# lte.net
KiCad netlist of a schematic drawn in Altium Designer
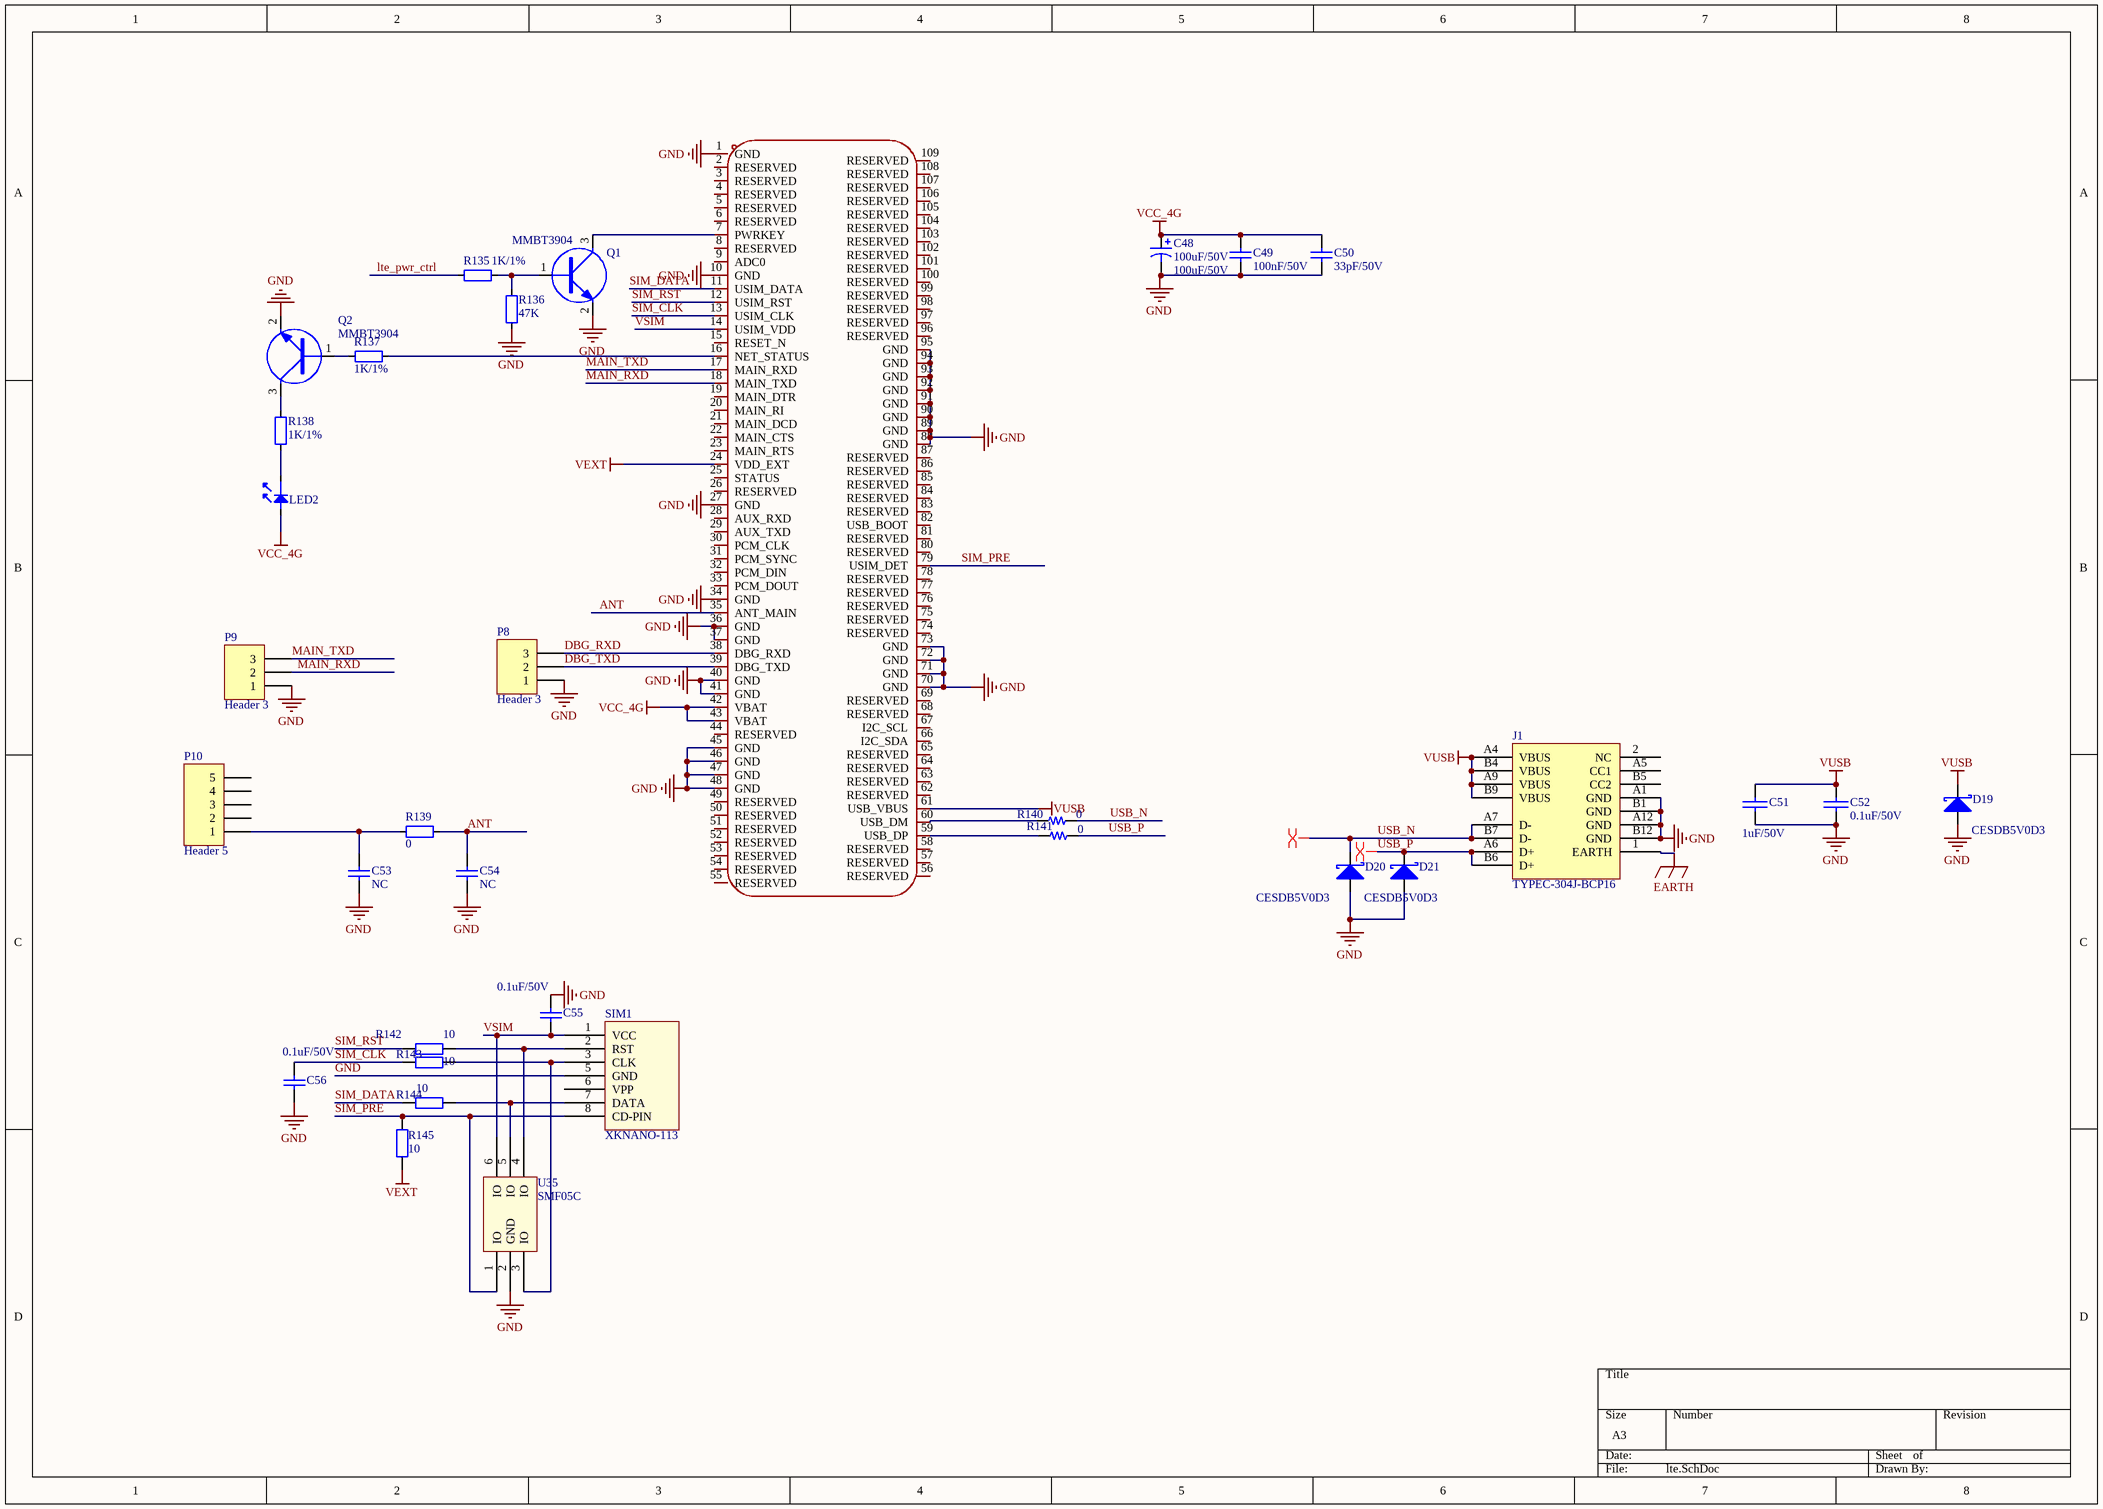
[diagram p0: lte.SchDoc]

(export (version "E")
  (design (tool "Eeschema 10.0.6"))
  (components
    (comp (ref "C48")
      (value "100uF/50V")
      (footprint "CAP-SMD_BD6.3-L6.5-W6.5-LS7.0-FD:CAP-SMD_BD6.3-L6.5-W6.5-LS7.0-FD")
      (description "Polarized Capacitor (Surface Mount)")
      (fields (field (name "ALTIUM_VALUE") "100uF/50V"))
      (libsource (lib "Miscellaneous Devices") (part "Cap Pol3"))
    )
    (comp (ref "C49")
      (value "100nF/50V")
      (footprint "0603C")
      (description "Capacitor")
      (libsource (lib "Miscellaneous Devices") (part "Cap"))
    )
    (comp (ref "C50")
      (value "33pF/50V")
      (footprint "0603C")
      (description "Capacitor")
      (libsource (lib "Miscellaneous Devices") (part "Cap"))
    )
    (comp (ref "C51")
      (value "1uF/50V")
      (footprint "CAPC1608X092N_0603")
      (fields (field (name "PARTNUMBER") "CL10A105KB8NNNC"))
      (libsource (lib "SM") (part "CAP"))
    )
    (comp (ref "C52")
      (value "0.1uF/50V")
      (footprint "CAPC1608X092N_0603")
      (fields (field (name "PARTNUMBER") "CC0603KRX7R9BB104"))
      (libsource (lib "SM") (part "CAP"))
    )
    (comp (ref "C53")
      (value "NC")
      (footprint "0603c")
      (description "Capacitor")
      (libsource (lib "Miscellaneous Devices") (part "Cap"))
    )
    (comp (ref "C54")
      (value "NC")
      (footprint "0603c")
      (description "Capacitor")
      (libsource (lib "Miscellaneous Devices") (part "Cap"))
    )
    (comp (ref "C55")
      (value "0.1uF/50V")
      (footprint "0603c")
      (description "Capacitor")
      (libsource (lib "Miscellaneous Devices") (part "Cap"))
    )
    (comp (ref "C56")
      (value "0.1uF/50V")
      (footprint "0603c")
      (description "Capacitor")
      (libsource (lib "Miscellaneous Devices") (part "Cap"))
    )
    (comp (ref "D19") (value "CESDB5V0D3") (footprint "SOD323") (libsource (lib "*") (part "DIODE S")))
    (comp (ref "D20") (value "CESDB5V0D3") (footprint "SOD323") (libsource (lib "*") (part "DIODE S")))
    (comp (ref "D21") (value "CESDB5V0D3") (footprint "SOD323") (libsource (lib "*") (part "DIODE S")))
    (comp (ref "J1")
      (value "TYPEC-304J-BCP16")
      (footprint "TYPEC_16P")
      (libsource (lib "Schlib_20110825") (part "TYPE C_16P"))
    )
    (comp (ref "LED2")
      (value "LED_Green_19-217")
      (footprint "0603led")
      (libsource (lib "RC_M_D_00") (part "LED_Green_19-217"))
    )
    (comp (ref "P8")
      (value "Header 3")
      (footprint "HDR1X3")
      (description "Header, 3-Pin")
      (libsource (lib "Miscellaneous Connectors") (part "Header 3"))
    )
    (comp (ref "P9")
      (value "Header 3")
      (footprint "HDR1X3")
      (description "Header, 3-Pin")
      (libsource (lib "Miscellaneous Connectors") (part "Header 3"))
    )
    (comp (ref "P10")
      (value "Header 5")
      (footprint "controller_V1.3.1:KH-SMA-KE-Z")
      (description "Header, 5-Pin")
      (libsource (lib "Miscellaneous Connectors") (part "Header 5"))
    )
    (comp (ref "Q1")
      (value "MMBT3904")
      (footprint "SOT23-3")
      (libsource (lib "CenLib") (part "NPN_MMBT3904"))
    )
    (comp (ref "Q2")
      (value "MMBT3904")
      (footprint "SOT23-3")
      (libsource (lib "CenLib") (part "NPN_MMBT3904"))
    )
    (comp (ref "R135") (value "1K/1%") (footprint "0603R") (libsource (lib "RC_M_D_00") (part "RES0603")))
    (comp (ref "R136") (value "47K") (footprint "0603r") (libsource (lib "RC_M_D_00") (part "RES0603")))
    (comp (ref "R137") (value "1K/1%") (footprint "0603r") (libsource (lib "RC_M_D_00") (part "RES0603")))
    (comp (ref "R138") (value "1K/1%") (footprint "0603R") (libsource (lib "RC_M_D_00") (part "RES0603")))
    (comp (ref "R139") (value "0") (footprint "0603r") (libsource (lib "RC_M_D_00") (part "RES0603")))
    (comp (ref "R140")
      (value "0")
      (footprint "RESC1608X055N_0603")
      (fields (field (name "PARTNUMBER") "RC0603FR-071KL"))
      (libsource (lib "JRJ_1") (part "R"))
    )
    (comp (ref "R141")
      (value "0")
      (footprint "RESC1608X055N_0603")
      (fields (field (name "PARTNUMBER") "RC0603FR-071KL"))
      (libsource (lib "JRJ_1") (part "R"))
    )
    (comp (ref "R142")
      (value "10")
      (footprint "0603r")
      (description "Resistor")
      (libsource (lib "Miscellaneous Devices") (part "Res2"))
    )
    (comp (ref "R143")
      (value "10")
      (footprint "0603r")
      (description "Resistor")
      (libsource (lib "Miscellaneous Devices") (part "Res2"))
    )
    (comp (ref "R144")
      (value "10")
      (footprint "0603r")
      (description "Resistor")
      (libsource (lib "Miscellaneous Devices") (part "Res2"))
    )
    (comp (ref "R145")
      (value "10")
      (footprint "0603r")
      (description "Resistor")
      (libsource (lib "") (part "Res2_1"))
    )
    (comp (ref "SIM1") (value "XKNANO-113") (footprint "Nano SIM") (libsource (lib "lm") (part "nano sim")))
    (comp (ref "U34")
      (value "EC800ECNNQ-N03-SNNSA")
      (footprint "LCC-LGA-109_L17.7-W15.8-P1.10_MC661:LCC-LGA-109_L17.7-W15.8-P1.10_MC661")
      (libsource (lib "altium-import") (part "root_0_EC800ECNNQ-N03-SNNSA_"))
    )
    (comp (ref "U35") (value "SMF05C") (footprint "sc70-6l") (libsource (lib "lm") (part "SMF05C")))
  )
  (nets
    (net (code "1") (name "/ANT") (class "Default")
      (node (ref "C54") (pin "1") (pinfunction "1_1") (pintype "passive"))
      (node (ref "R139") (pin "1") (pinfunction "1_1") (pintype "passive"))
      (node (ref "U34") (pin "35") (pinfunction "ANT_MAIN_35") (pintype "passive"))
    )
    (net (code "2") (name "/DBG_RXD") (class "Default")
      (node (ref "P8") (pin "3") (pinfunction "3_3") (pintype "passive"))
      (node (ref "U34") (pin "38") (pinfunction "DBG_RXD_38") (pintype "passive"))
    )
    (net (code "3") (name "/DBG_TXD") (class "Default")
      (node (ref "P8") (pin "2") (pinfunction "2_2") (pintype "passive"))
      (node (ref "U34") (pin "39") (pinfunction "DBG_TXD_39") (pintype "passive"))
    )
    (net (code "4") (name "/MAIN_RXD") (class "Default")
      (node (ref "P9") (pin "2") (pinfunction "2_2") (pintype "passive"))
      (node (ref "U34") (pin "18") (pinfunction "MAIN_TXD_18") (pintype "passive"))
    )
    (net (code "5") (name "/MAIN_TXD") (class "Default")
      (node (ref "P9") (pin "3") (pinfunction "3_3") (pintype "passive"))
      (node (ref "U34") (pin "17") (pinfunction "MAIN_RXD_17") (pintype "passive"))
    )
    (net (code "6") (name "/SIM_CLK") (class "Default")
      (node (ref "C56") (pin "1") (pinfunction "1_1") (pintype "passive"))
      (node (ref "R143") (pin "2") (pinfunction "2_2") (pintype "passive"))
      (node (ref "U34") (pin "13") (pinfunction "USIM_CLK_13") (pintype "passive"))
    )
    (net (code "7") (name "/SIM_DATA") (class "Default")
      (node (ref "R144") (pin "2") (pinfunction "2_2") (pintype "passive"))
      (node (ref "U34") (pin "11") (pinfunction "USIM_DATA_11") (pintype "passive"))
    )
    (net (code "8") (name "/SIM_PRE") (class "Default")
      (node (ref "R145") (pin "1") (pinfunction "1_1") (pintype "passive"))
      (node (ref "SIM1") (pin "8") (pinfunction "CD-PIN_8") (pintype "passive"))
      (node (ref "U34") (pin "79") (pinfunction "USIM_DET_79") (pintype "passive"))
      (node (ref "U35") (pin "1") (pinfunction "IO_1") (pintype "passive"))
    )
    (net (code "9") (name "/SIM_RST") (class "Default")
      (node (ref "R142") (pin "2") (pinfunction "2_2") (pintype "passive"))
      (node (ref "U34") (pin "12") (pinfunction "USIM_RST_12") (pintype "passive"))
    )
    (net (code "10") (name "/USB_N") (class "Default")
      (node (ref "D20") (pin "2") (pinfunction "K_2") (pintype "passive"))
      (node (ref "J1") (pin "A7") (pinfunction "D-_A7") (pintype "passive"))
      (node (ref "J1") (pin "B7") (pinfunction "D-_B7") (pintype "passive"))
      (node (ref "R140") (pin "1") (pintype "passive"))
    )
    (net (code "11") (name "/USB_P") (class "Default")
      (node (ref "D21") (pin "2") (pinfunction "K_2") (pintype "passive"))
      (node (ref "J1") (pin "A6") (pinfunction "D+_A6") (pintype "passive"))
      (node (ref "J1") (pin "B6") (pinfunction "D+_B6") (pintype "passive"))
      (node (ref "R141") (pin "1") (pintype "passive"))
    )
    (net (code "12") (name "/VSIM") (class "Default")
      (node (ref "C55") (pin "2") (pinfunction "2_2") (pintype "passive"))
      (node (ref "SIM1") (pin "1") (pinfunction "VCC_1") (pintype "passive"))
      (node (ref "U34") (pin "14") (pinfunction "USIM_VDD_14") (pintype "passive"))
      (node (ref "U35") (pin "6") (pinfunction "IO_6") (pintype "passive"))
    )
    (net (code "13") (name "/lte_pwr_ctrl") (class "Default")
      (node (ref "R135") (pin "1") (pinfunction "1_1") (pintype "passive"))
    )
    (net (code "14") (name "EARTH") (class "Default")
      (node (ref "J1") (pin "1") (pinfunction "EARTH_1") (pintype "passive"))
    )
    (net (code "15") (name "GND") (class "Default")
      (node (ref "C48") (pin "2") (pinfunction "2_2") (pintype "passive"))
      (node (ref "C49") (pin "1") (pinfunction "1_1") (pintype "passive"))
      (node (ref "C50") (pin "1") (pinfunction "1_1") (pintype "passive"))
      (node (ref "C51") (pin "1") (pinfunction "1_1") (pintype "passive"))
      (node (ref "C52") (pin "1") (pinfunction "1_1") (pintype "passive"))
      (node (ref "C53") (pin "2") (pinfunction "2_2") (pintype "passive"))
      (node (ref "C54") (pin "2") (pinfunction "2_2") (pintype "passive"))
      (node (ref "C55") (pin "1") (pinfunction "1_1") (pintype "passive"))
      (node (ref "C56") (pin "2") (pinfunction "2_2") (pintype "passive"))
      (node (ref "D19") (pin "1") (pinfunction "A_1") (pintype "passive"))
      (node (ref "D20") (pin "1") (pinfunction "A_1") (pintype "passive"))
      (node (ref "D21") (pin "1") (pinfunction "A_1") (pintype "passive"))
      (node (ref "J1") (pin "A1") (pinfunction "GND_A1") (pintype "passive"))
      (node (ref "J1") (pin "A12") (pinfunction "GND_A12") (pintype "passive"))
      (node (ref "J1") (pin "B1") (pinfunction "GND_B1") (pintype "passive"))
      (node (ref "J1") (pin "B12") (pinfunction "GND_B12") (pintype "passive"))
      (node (ref "P8") (pin "1") (pinfunction "1_1") (pintype "passive"))
      (node (ref "P9") (pin "1") (pinfunction "1_1") (pintype "passive"))
      (node (ref "Q1") (pin "2") (pinfunction "E_2") (pintype "passive"))
      (node (ref "Q2") (pin "2") (pinfunction "E_2") (pintype "passive"))
      (node (ref "R136") (pin "1") (pinfunction "1_1") (pintype "passive"))
      (node (ref "SIM1") (pin "5") (pinfunction "GND_5") (pintype "passive"))
      (node (ref "U34") (pin "1") (pinfunction "GND_1") (pintype "passive"))
      (node (ref "U34") (pin "10") (pinfunction "GND_10") (pintype "passive"))
      (node (ref "U34") (pin "27") (pinfunction "GND_27") (pintype "passive"))
      (node (ref "U34") (pin "34") (pinfunction "GND_34") (pintype "passive"))
      (node (ref "U34") (pin "36") (pinfunction "GND_36") (pintype "passive"))
      (node (ref "U34") (pin "37") (pinfunction "GND_37") (pintype "passive"))
      (node (ref "U34") (pin "40") (pinfunction "GND_40") (pintype "passive"))
      (node (ref "U34") (pin "41") (pinfunction "GND_41") (pintype "passive"))
      (node (ref "U34") (pin "45") (pinfunction "GND_45") (pintype "passive"))
      (node (ref "U34") (pin "46") (pinfunction "GND_46") (pintype "passive"))
      (node (ref "U34") (pin "47") (pinfunction "GND_47") (pintype "passive"))
      (node (ref "U34") (pin "48") (pinfunction "GND_48") (pintype "passive"))
      (node (ref "U34") (pin "70") (pinfunction "GND_70") (pintype "passive"))
      (node (ref "U34") (pin "71") (pinfunction "GND_71") (pintype "passive"))
      (node (ref "U34") (pin "72") (pinfunction "GND_72") (pintype "passive"))
      (node (ref "U34") (pin "73") (pinfunction "GND_73") (pintype "passive"))
      (node (ref "U34") (pin "88") (pinfunction "GND_88") (pintype "passive"))
      (node (ref "U34") (pin "89") (pinfunction "GND_89") (pintype "passive"))
      (node (ref "U34") (pin "90") (pinfunction "GND_90") (pintype "passive"))
      (node (ref "U34") (pin "91") (pinfunction "GND_91") (pintype "passive"))
      (node (ref "U34") (pin "92") (pinfunction "GND_92") (pintype "passive"))
      (node (ref "U34") (pin "93") (pinfunction "GND_93") (pintype "passive"))
      (node (ref "U34") (pin "94") (pinfunction "GND_94") (pintype "passive"))
      (node (ref "U34") (pin "95") (pinfunction "GND_95") (pintype "passive"))
      (node (ref "U35") (pin "2") (pinfunction "GND_2") (pintype "passive"))
    )
    (net (code "16") (name "Net-(C53-Pad1)") (class "Default")
      (node (ref "C53") (pin "1") (pinfunction "1_1") (pintype "passive"))
      (node (ref "P10") (pin "1") (pinfunction "1_1") (pintype "passive"))
      (node (ref "R139") (pin "2") (pinfunction "2_2") (pintype "passive"))
    )
    (net (code "17") (name "Net-(LED2-Pad2)") (class "Default")
      (node (ref "LED2") (pin "2") (pinfunction "2_2") (pintype "passive"))
      (node (ref "R138") (pin "1") (pinfunction "1_1") (pintype "passive"))
    )
    (net (code "18") (name "Net-(Q1-B)") (class "Default")
      (node (ref "Q1") (pin "1") (pinfunction "B_1") (pintype "passive"))
      (node (ref "R135") (pin "2") (pinfunction "2_2") (pintype "passive"))
      (node (ref "R136") (pin "2") (pinfunction "2_2") (pintype "passive"))
    )
    (net (code "19") (name "Net-(Q1-C)") (class "Default")
      (node (ref "Q1") (pin "3") (pinfunction "C_3") (pintype "passive"))
      (node (ref "U34") (pin "7") (pinfunction "PWRKEY_7") (pintype "passive"))
    )
    (net (code "20") (name "Net-(Q2-B)") (class "Default")
      (node (ref "Q2") (pin "1") (pinfunction "B_1") (pintype "passive"))
      (node (ref "R137") (pin "2") (pinfunction "2_2") (pintype "passive"))
    )
    (net (code "21") (name "Net-(Q2-C)") (class "Default")
      (node (ref "Q2") (pin "3") (pinfunction "C_3") (pintype "passive"))
      (node (ref "R138") (pin "2") (pinfunction "2_2") (pintype "passive"))
    )
    (net (code "22") (name "Net-(SIM1-CLK)") (class "Default")
      (node (ref "R143") (pin "1") (pinfunction "1_1") (pintype "passive"))
      (node (ref "SIM1") (pin "3") (pinfunction "CLK_3") (pintype "passive"))
      (node (ref "U35") (pin "3") (pinfunction "IO_3") (pintype "passive"))
    )
    (net (code "23") (name "Net-(SIM1-DATA)") (class "Default")
      (node (ref "R144") (pin "1") (pinfunction "1_1") (pintype "passive"))
      (node (ref "SIM1") (pin "7") (pinfunction "DATA_7") (pintype "passive"))
      (node (ref "U35") (pin "5") (pinfunction "IO_5") (pintype "passive"))
    )
    (net (code "24") (name "Net-(SIM1-RST)") (class "Default")
      (node (ref "R142") (pin "1") (pinfunction "1_1") (pintype "passive"))
      (node (ref "SIM1") (pin "2") (pinfunction "RST_2") (pintype "passive"))
      (node (ref "U35") (pin "4") (pinfunction "IO_4") (pintype "passive"))
    )
    (net (code "25") (name "Net-(U34-NET_STATUS)") (class "Default")
      (node (ref "R137") (pin "1") (pinfunction "1_1") (pintype "passive"))
      (node (ref "U34") (pin "16") (pinfunction "NET_STATUS_16") (pintype "passive"))
    )
    (net (code "26") (name "Net-(U34-USB_DM)") (class "Default")
      (node (ref "R140") (pin "2") (pintype "passive"))
      (node (ref "U34") (pin "60") (pinfunction "USB_DM_60") (pintype "passive"))
    )
    (net (code "27") (name "Net-(U34-USB_DP)") (class "Default")
      (node (ref "R141") (pin "2") (pintype "passive"))
      (node (ref "U34") (pin "59") (pinfunction "USB_DP_59") (pintype "passive"))
    )
    (net (code "28") (name "VCC_4G") (class "Default")
      (node (ref "C48") (pin "1") (pinfunction "1_1") (pintype "passive"))
      (node (ref "C49") (pin "2") (pinfunction "2_2") (pintype "passive"))
      (node (ref "C50") (pin "2") (pinfunction "2_2") (pintype "passive"))
      (node (ref "LED2") (pin "1") (pinfunction "1_1") (pintype "passive"))
      (node (ref "U34") (pin "42") (pinfunction "VBAT_42") (pintype "passive"))
      (node (ref "U34") (pin "43") (pinfunction "VBAT_43") (pintype "passive"))
    )
    (net (code "29") (name "VEXT") (class "Default")
      (node (ref "R145") (pin "2") (pinfunction "2_2") (pintype "passive"))
      (node (ref "U34") (pin "24") (pinfunction "VDD_EXT_24") (pintype "passive"))
    )
    (net (code "30") (name "VUSB") (class "Default")
      (node (ref "C51") (pin "2") (pinfunction "2_2") (pintype "passive"))
      (node (ref "C52") (pin "2") (pinfunction "2_2") (pintype "passive"))
      (node (ref "D19") (pin "2") (pinfunction "K_2") (pintype "passive"))
      (node (ref "J1") (pin "A4") (pinfunction "VBUS_A4") (pintype "passive"))
      (node (ref "J1") (pin "A9") (pinfunction "VBUS_A9") (pintype "passive"))
      (node (ref "J1") (pin "B4") (pinfunction "VBUS_B4") (pintype "passive"))
      (node (ref "J1") (pin "B9") (pinfunction "VBUS_B9") (pintype "passive"))
      (node (ref "U34") (pin "61") (pinfunction "USB_VBUS_61") (pintype "passive"))
    )
    (net (code "31") (name "unconnected-(J1-CC1-PadA5)") (class "Default")
      (node (ref "J1") (pin "A5") (pinfunction "CC1_A5") (pintype "passive"))
    )
    (net (code "32") (name "unconnected-(J1-CC2-PadB5)") (class "Default")
      (node (ref "J1") (pin "B5") (pinfunction "CC2_B5") (pintype "passive"))
    )
    (net (code "33") (name "unconnected-(J1-NC-Pad2)") (class "Default")
      (node (ref "J1") (pin "2") (pinfunction "NC_2") (pintype "passive"))
    )
    (net (code "34") (name "unconnected-(P10-Pad2)") (class "Default")
      (node (ref "P10") (pin "2") (pinfunction "2_2") (pintype "passive"))
    )
    (net (code "35") (name "unconnected-(P10-Pad3)") (class "Default")
      (node (ref "P10") (pin "3") (pinfunction "3_3") (pintype "passive"))
    )
    (net (code "36") (name "unconnected-(P10-Pad4)") (class "Default")
      (node (ref "P10") (pin "4") (pinfunction "4_4") (pintype "passive"))
    )
    (net (code "37") (name "unconnected-(P10-Pad5)") (class "Default")
      (node (ref "P10") (pin "5") (pinfunction "5_5") (pintype "passive"))
    )
    (net (code "38") (name "unconnected-(SIM1-VPP-Pad6)") (class "Default")
      (node (ref "SIM1") (pin "6") (pinfunction "VPP_6") (pintype "passive"))
    )
    (net (code "39") (name "unconnected-(U34-ADC0-Pad9)") (class "Default")
      (node (ref "U34") (pin "9") (pinfunction "ADC0_9") (pintype "passive"))
    )
    (net (code "40") (name "unconnected-(U34-AUX_RXD-Pad28)") (class "Default")
      (node (ref "U34") (pin "28") (pinfunction "AUX_RXD_28") (pintype "passive"))
    )
    (net (code "41") (name "unconnected-(U34-AUX_TXD-Pad29)") (class "Default")
      (node (ref "U34") (pin "29") (pinfunction "AUX_TXD_29") (pintype "passive"))
    )
    (net (code "42") (name "unconnected-(U34-I2C_SCL-Pad67)") (class "Default")
      (node (ref "U34") (pin "67") (pinfunction "I2C_SCL_67") (pintype "passive"))
    )
    (net (code "43") (name "unconnected-(U34-I2C_SDA-Pad66)") (class "Default")
      (node (ref "U34") (pin "66") (pinfunction "I2C_SDA_66") (pintype "passive"))
    )
    (net (code "44") (name "unconnected-(U34-MAIN_CTS-Pad22)") (class "Default")
      (node (ref "U34") (pin "22") (pinfunction "MAIN_CTS_22") (pintype "passive"))
    )
    (net (code "45") (name "unconnected-(U34-MAIN_DCD-Pad21)") (class "Default")
      (node (ref "U34") (pin "21") (pinfunction "MAIN_DCD_21") (pintype "passive"))
    )
    (net (code "46") (name "unconnected-(U34-MAIN_DTR-Pad19)") (class "Default")
      (node (ref "U34") (pin "19") (pinfunction "MAIN_DTR_19") (pintype "passive"))
    )
    (net (code "47") (name "unconnected-(U34-MAIN_RI-Pad20)") (class "Default")
      (node (ref "U34") (pin "20") (pinfunction "MAIN_RI_20") (pintype "passive"))
    )
    (net (code "48") (name "unconnected-(U34-MAIN_RTS-Pad23)") (class "Default")
      (node (ref "U34") (pin "23") (pinfunction "MAIN_RTS_23") (pintype "passive"))
    )
    (net (code "49") (name "unconnected-(U34-PCM_CLK-Pad30)") (class "Default")
      (node (ref "U34") (pin "30") (pinfunction "PCM_CLK_30") (pintype "passive"))
    )
    (net (code "50") (name "unconnected-(U34-PCM_DIN-Pad32)") (class "Default")
      (node (ref "U34") (pin "32") (pinfunction "PCM_DIN_32") (pintype "passive"))
    )
    (net (code "51") (name "unconnected-(U34-PCM_DOUT-Pad33)") (class "Default")
      (node (ref "U34") (pin "33") (pinfunction "PCM_DOUT_33") (pintype "passive"))
    )
    (net (code "52") (name "unconnected-(U34-PCM_SYNC-Pad31)") (class "Default")
      (node (ref "U34") (pin "31") (pinfunction "PCM_SYNC_31") (pintype "passive"))
    )
    (net (code "53") (name "unconnected-(U34-RESERVED-Pad2)") (class "Default")
      (node (ref "U34") (pin "2") (pinfunction "RESERVED_2") (pintype "passive"))
    )
    (net (code "54") (name "unconnected-(U34-RESERVED-Pad3)") (class "Default")
      (node (ref "U34") (pin "3") (pinfunction "RESERVED_3") (pintype "passive"))
    )
    (net (code "55") (name "unconnected-(U34-RESERVED-Pad4)") (class "Default")
      (node (ref "U34") (pin "4") (pinfunction "RESERVED_4") (pintype "passive"))
    )
    (net (code "56") (name "unconnected-(U34-RESERVED-Pad5)") (class "Default")
      (node (ref "U34") (pin "5") (pinfunction "RESERVED_5") (pintype "passive"))
    )
    (net (code "57") (name "unconnected-(U34-RESERVED-Pad6)") (class "Default")
      (node (ref "U34") (pin "6") (pinfunction "RESERVED_6") (pintype "passive"))
    )
    (net (code "58") (name "unconnected-(U34-RESERVED-Pad8)") (class "Default")
      (node (ref "U34") (pin "8") (pinfunction "RESERVED_8") (pintype "passive"))
    )
    (net (code "59") (name "unconnected-(U34-RESERVED-Pad26)") (class "Default")
      (node (ref "U34") (pin "26") (pinfunction "RESERVED_26") (pintype "passive"))
    )
    (net (code "60") (name "unconnected-(U34-RESERVED-Pad44)") (class "Default")
      (node (ref "U34") (pin "44") (pinfunction "RESERVED_44") (pintype "passive"))
    )
    (net (code "61") (name "unconnected-(U34-RESERVED-Pad49)") (class "Default")
      (node (ref "U34") (pin "49") (pinfunction "RESERVED_49") (pintype "passive"))
    )
    (net (code "62") (name "unconnected-(U34-RESERVED-Pad50)") (class "Default")
      (node (ref "U34") (pin "50") (pinfunction "RESERVED_50") (pintype "passive"))
    )
    (net (code "63") (name "unconnected-(U34-RESERVED-Pad51)") (class "Default")
      (node (ref "U34") (pin "51") (pinfunction "RESERVED_51") (pintype "passive"))
    )
    (net (code "64") (name "unconnected-(U34-RESERVED-Pad52)") (class "Default")
      (node (ref "U34") (pin "52") (pinfunction "RESERVED_52") (pintype "passive"))
    )
    (net (code "65") (name "unconnected-(U34-RESERVED-Pad53)") (class "Default")
      (node (ref "U34") (pin "53") (pinfunction "RESERVED_53") (pintype "passive"))
    )
    (net (code "66") (name "unconnected-(U34-RESERVED-Pad54)") (class "Default")
      (node (ref "U34") (pin "54") (pinfunction "RESERVED_54") (pintype "passive"))
    )
    (net (code "67") (name "unconnected-(U34-RESERVED-Pad55)") (class "Default")
      (node (ref "U34") (pin "55") (pinfunction "RESERVED_55") (pintype "passive"))
    )
    (net (code "68") (name "unconnected-(U34-RESERVED-Pad56)") (class "Default")
      (node (ref "U34") (pin "56") (pinfunction "RESERVED_56") (pintype "passive"))
    )
    (net (code "69") (name "unconnected-(U34-RESERVED-Pad57)") (class "Default")
      (node (ref "U34") (pin "57") (pinfunction "RESERVED_57") (pintype "passive"))
    )
    (net (code "70") (name "unconnected-(U34-RESERVED-Pad58)") (class "Default")
      (node (ref "U34") (pin "58") (pinfunction "RESERVED_58") (pintype "passive"))
    )
    (net (code "71") (name "unconnected-(U34-RESERVED-Pad62)") (class "Default")
      (node (ref "U34") (pin "62") (pinfunction "RESERVED_62") (pintype "passive"))
    )
    (net (code "72") (name "unconnected-(U34-RESERVED-Pad63)") (class "Default")
      (node (ref "U34") (pin "63") (pinfunction "RESERVED_63") (pintype "passive"))
    )
    (net (code "73") (name "unconnected-(U34-RESERVED-Pad64)") (class "Default")
      (node (ref "U34") (pin "64") (pinfunction "RESERVED_64") (pintype "passive"))
    )
    (net (code "74") (name "unconnected-(U34-RESERVED-Pad65)") (class "Default")
      (node (ref "U34") (pin "65") (pinfunction "RESERVED_65") (pintype "passive"))
    )
    (net (code "75") (name "unconnected-(U34-RESERVED-Pad68)") (class "Default")
      (node (ref "U34") (pin "68") (pinfunction "RESERVED_68") (pintype "passive"))
    )
    (net (code "76") (name "unconnected-(U34-RESERVED-Pad69)") (class "Default")
      (node (ref "U34") (pin "69") (pinfunction "RESERVED_69") (pintype "passive"))
    )
    (net (code "77") (name "unconnected-(U34-RESERVED-Pad74)") (class "Default")
      (node (ref "U34") (pin "74") (pinfunction "RESERVED_74") (pintype "passive"))
    )
    (net (code "78") (name "unconnected-(U34-RESERVED-Pad75)") (class "Default")
      (node (ref "U34") (pin "75") (pinfunction "RESERVED_75") (pintype "passive"))
    )
    (net (code "79") (name "unconnected-(U34-RESERVED-Pad76)") (class "Default")
      (node (ref "U34") (pin "76") (pinfunction "RESERVED_76") (pintype "passive"))
    )
    (net (code "80") (name "unconnected-(U34-RESERVED-Pad77)") (class "Default")
      (node (ref "U34") (pin "77") (pinfunction "RESERVED_77") (pintype "passive"))
    )
    (net (code "81") (name "unconnected-(U34-RESERVED-Pad78)") (class "Default")
      (node (ref "U34") (pin "78") (pinfunction "RESERVED_78") (pintype "passive"))
    )
    (net (code "82") (name "unconnected-(U34-RESERVED-Pad80)") (class "Default")
      (node (ref "U34") (pin "80") (pinfunction "RESERVED_80") (pintype "passive"))
    )
    (net (code "83") (name "unconnected-(U34-RESERVED-Pad81)") (class "Default")
      (node (ref "U34") (pin "81") (pinfunction "RESERVED_81") (pintype "passive"))
    )
    (net (code "84") (name "unconnected-(U34-RESERVED-Pad83)") (class "Default")
      (node (ref "U34") (pin "83") (pinfunction "RESERVED_83") (pintype "passive"))
    )
    (net (code "85") (name "unconnected-(U34-RESERVED-Pad84)") (class "Default")
      (node (ref "U34") (pin "84") (pinfunction "RESERVED_84") (pintype "passive"))
    )
    (net (code "86") (name "unconnected-(U34-RESERVED-Pad85)") (class "Default")
      (node (ref "U34") (pin "85") (pinfunction "RESERVED_85") (pintype "passive"))
    )
    (net (code "87") (name "unconnected-(U34-RESERVED-Pad86)") (class "Default")
      (node (ref "U34") (pin "86") (pinfunction "RESERVED_86") (pintype "passive"))
    )
    (net (code "88") (name "unconnected-(U34-RESERVED-Pad87)") (class "Default")
      (node (ref "U34") (pin "87") (pinfunction "RESERVED_87") (pintype "passive"))
    )
    (net (code "89") (name "unconnected-(U34-RESERVED-Pad96)") (class "Default")
      (node (ref "U34") (pin "96") (pinfunction "RESERVED_96") (pintype "passive"))
    )
    (net (code "90") (name "unconnected-(U34-RESERVED-Pad97)") (class "Default")
      (node (ref "U34") (pin "97") (pinfunction "RESERVED_97") (pintype "passive"))
    )
    (net (code "91") (name "unconnected-(U34-RESERVED-Pad98)") (class "Default")
      (node (ref "U34") (pin "98") (pinfunction "RESERVED_98") (pintype "passive"))
    )
    (net (code "92") (name "unconnected-(U34-RESERVED-Pad99)") (class "Default")
      (node (ref "U34") (pin "99") (pinfunction "RESERVED_99") (pintype "passive"))
    )
    (net (code "93") (name "unconnected-(U34-RESERVED-Pad100)") (class "Default")
      (node (ref "U34") (pin "100") (pinfunction "RESERVED_100") (pintype "passive"))
    )
    (net (code "94") (name "unconnected-(U34-RESERVED-Pad101)") (class "Default")
      (node (ref "U34") (pin "101") (pinfunction "RESERVED_101") (pintype "passive"))
    )
    (net (code "95") (name "unconnected-(U34-RESERVED-Pad102)") (class "Default")
      (node (ref "U34") (pin "102") (pinfunction "RESERVED_102") (pintype "passive"))
    )
    (net (code "96") (name "unconnected-(U34-RESERVED-Pad103)") (class "Default")
      (node (ref "U34") (pin "103") (pinfunction "RESERVED_103") (pintype "passive"))
    )
    (net (code "97") (name "unconnected-(U34-RESERVED-Pad104)") (class "Default")
      (node (ref "U34") (pin "104") (pinfunction "RESERVED_104") (pintype "passive"))
    )
    (net (code "98") (name "unconnected-(U34-RESERVED-Pad105)") (class "Default")
      (node (ref "U34") (pin "105") (pinfunction "RESERVED_105") (pintype "passive"))
    )
    (net (code "99") (name "unconnected-(U34-RESERVED-Pad106)") (class "Default")
      (node (ref "U34") (pin "106") (pinfunction "RESERVED_106") (pintype "passive"))
    )
    (net (code "100") (name "unconnected-(U34-RESERVED-Pad107)") (class "Default")
      (node (ref "U34") (pin "107") (pinfunction "RESERVED_107") (pintype "passive"))
    )
    (net (code "101") (name "unconnected-(U34-RESERVED-Pad108)") (class "Default")
      (node (ref "U34") (pin "108") (pinfunction "RESERVED_108") (pintype "passive"))
    )
    (net (code "102") (name "unconnected-(U34-RESERVED-Pad109)") (class "Default")
      (node (ref "U34") (pin "109") (pinfunction "RESERVED_109") (pintype "passive"))
    )
    (net (code "103") (name "unconnected-(U34-RESET_N-Pad15)") (class "Default")
      (node (ref "U34") (pin "15") (pinfunction "RESET_N_15") (pintype "passive"))
    )
    (net (code "104") (name "unconnected-(U34-STATUS-Pad25)") (class "Default")
      (node (ref "U34") (pin "25") (pinfunction "STATUS_25") (pintype "passive"))
    )
    (net (code "105") (name "unconnected-(U34-USB_BOOT-Pad82)") (class "Default")
      (node (ref "U34") (pin "82") (pinfunction "USB_BOOT_82") (pintype "passive"))
    )
  )
)
